# PLL_ADF4169.net
KiCad netlist of a schematic drawn in Altium Designer
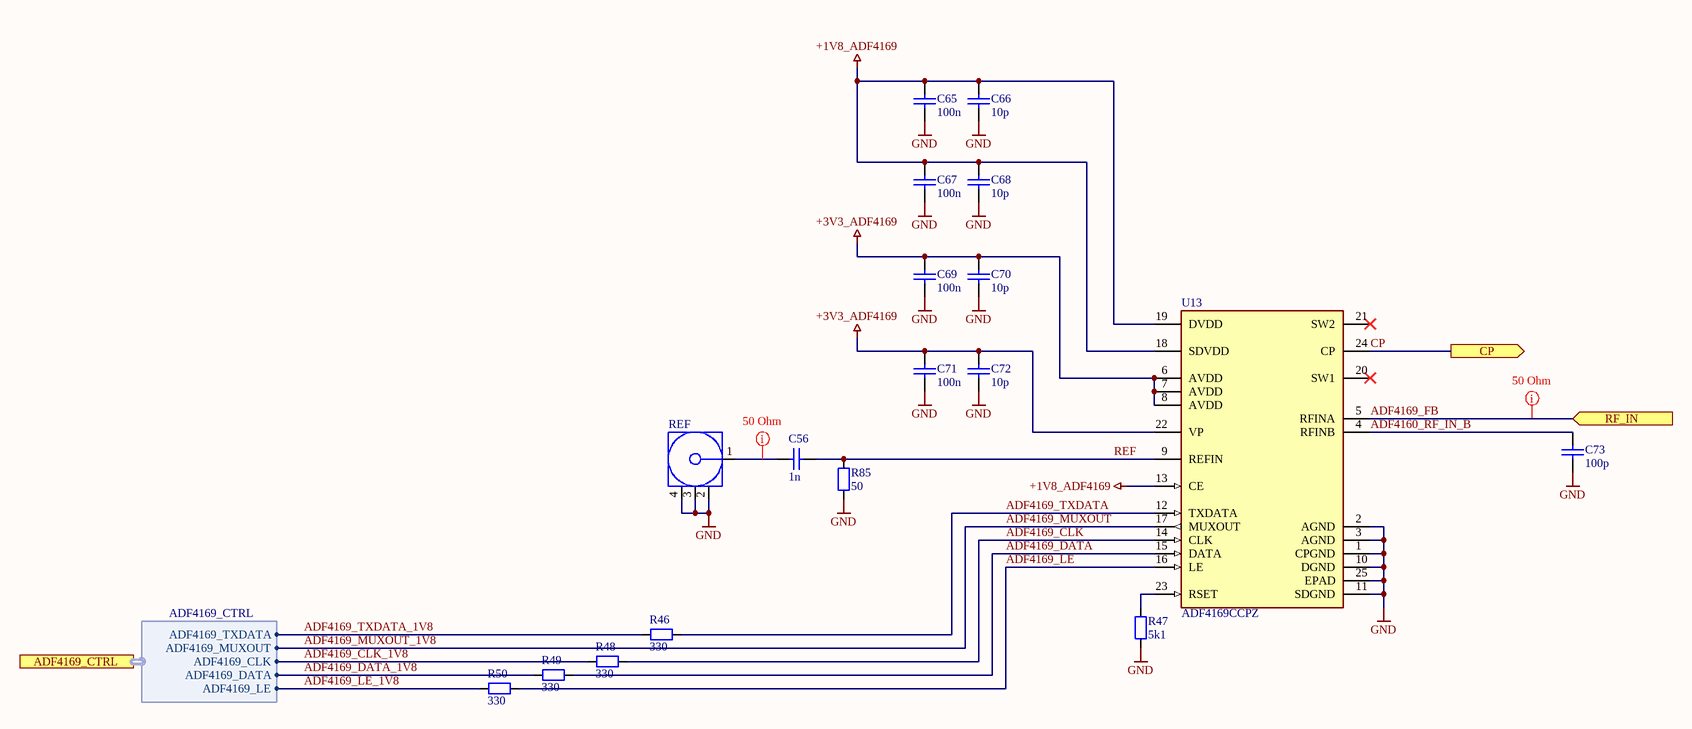
[diagram p0: PLL_ADF4169.SchDoc]

(export (version "E")
  (design (tool "Eeschema 10.0.6"))
  (components
    (comp (ref "C56")
      (value "1n")
      (footprint "C_0402_1005Metric_IPC_N")
      (description "Generic MLCC with 0402 Footprint")
      (fields (field (name "TOLERANCE") "5%"))
      (libsource (lib "database_library") (part "Capacitor_unpol"))
    )
    (comp (ref "C65")
      (value "100n")
      (footprint "C_0402_1005Metric_IPC_N")
      (description "Generic MLCC with 0402 Footprint")
      (fields (field (name "TOLERANCE") "10%"))
      (libsource (lib "database_library") (part "Capacitor_unpol"))
    )
    (comp (ref "C66")
      (value "10p")
      (footprint "C_0402_1005Metric_IPC_N")
      (description "Generic MLCC with 0402 Footprint")
      (fields (field (name "TOLERANCE") "0.5p"))
      (libsource (lib "database_library") (part "Capacitor_unpol"))
    )
    (comp (ref "C67")
      (value "100n")
      (footprint "C_0402_1005Metric_IPC_N")
      (description "Generic MLCC with 0402 Footprint")
      (fields (field (name "TOLERANCE") "10%"))
      (libsource (lib "database_library") (part "Capacitor_unpol"))
    )
    (comp (ref "C68")
      (value "10p")
      (footprint "C_0402_1005Metric_IPC_N")
      (description "Generic MLCC with 0402 Footprint")
      (fields (field (name "TOLERANCE") "0.5p"))
      (libsource (lib "database_library") (part "Capacitor_unpol"))
    )
    (comp (ref "C69")
      (value "100n")
      (footprint "C_0402_1005Metric_IPC_N")
      (description "Generic MLCC with 0402 Footprint")
      (fields (field (name "TOLERANCE") "10%"))
      (libsource (lib "database_library") (part "Capacitor_unpol"))
    )
    (comp (ref "C70")
      (value "10p")
      (footprint "C_0402_1005Metric_IPC_N")
      (description "Generic MLCC with 0402 Footprint")
      (fields (field (name "TOLERANCE") "0.5p"))
      (libsource (lib "database_library") (part "Capacitor_unpol"))
    )
    (comp (ref "C71")
      (value "100n")
      (footprint "C_0402_1005Metric_IPC_N")
      (description "Generic MLCC with 0402 Footprint")
      (fields (field (name "TOLERANCE") "10%"))
      (libsource (lib "database_library") (part "Capacitor_unpol"))
    )
    (comp (ref "C72")
      (value "10p")
      (footprint "C_0402_1005Metric_IPC_N")
      (description "Generic MLCC with 0402 Footprint")
      (fields (field (name "TOLERANCE") "0.5p"))
      (libsource (lib "database_library") (part "Capacitor_unpol"))
    )
    (comp (ref "C73")
      (value "100p")
      (footprint "C_0402_1005Metric_IPC_N")
      (description "Generic MLCC with 0402 Footprint")
      (libsource (lib "database_library") (part "Capacitor_unpol"))
    )
    (comp (ref "R46")
      (value "330")
      (footprint "R_0402_1005Metric_IPC_N")
      (description "Generic Chip Resistor with 0402 Footprint")
      (libsource (lib "database_library") (part "Resistor"))
    )
    (comp (ref "R47")
      (value "5k1")
      (footprint "R_0402_1005Metric_IPC_N")
      (description "Generic Chip Resistor with 0402 Footprint")
      (fields (field (name "TOLERANCE") "1%"))
      (libsource (lib "database_library") (part "Resistor"))
    )
    (comp (ref "R48")
      (value "330")
      (footprint "R_0402_1005Metric_IPC_N")
      (description "Generic Chip Resistor with 0402 Footprint")
      (libsource (lib "database_library") (part "Resistor"))
    )
    (comp (ref "R49")
      (value "330")
      (footprint "R_0402_1005Metric_IPC_N")
      (description "Generic Chip Resistor with 0402 Footprint")
      (libsource (lib "database_library") (part "Resistor"))
    )
    (comp (ref "R50")
      (value "330")
      (footprint "R_0402_1005Metric_IPC_N")
      (description "Generic Chip Resistor with 0402 Footprint")
      (libsource (lib "database_library") (part "Resistor"))
    )
    (comp (ref "R85")
      (value "50")
      (footprint "R_0402_1005Metric_IPC_N")
      (description "Generic Chip Resistor with 0402 Footprint")
      (libsource (lib "database_library") (part "Resistor"))
    )
    (comp (ref "REF")
      (value "60312862112552")
      (footprint "60312862112552")
      (description "WR-SMA Connector, PCB Solderless, DC~18GHz, 50Ohm")
      (fields (field (name "MANUFACTURER") "Würth"))
      (libsource (lib "database_library") (part "60312862112552"))
    )
    (comp (ref "U13")
      (value "ADF4169CCPZ")
      (footprint "LFCSP-WQ-24-1EP_4x4mm_P0.5mm_EP2.1x2.1mm_IPC_N")
      (fields (field (name "MANUFACTURER") "Analog Devices"))
      (libsource (lib "database_library") (part "ADF4169"))
    )
  )
  (nets
    (net (code "2") (name "+1V8_ADF4169") (class "Default")
      (node (ref "C65") (pin "2") (pinfunction "2_2") (pintype "passive"))
      (node (ref "C66") (pin "2") (pinfunction "2_2") (pintype "passive"))
      (node (ref "C67") (pin "2") (pinfunction "2_2") (pintype "passive"))
      (node (ref "C68") (pin "2") (pinfunction "2_2") (pintype "passive"))
      (node (ref "U13") (pin "13") (pinfunction "CE_13") (pintype "input"))
      (node (ref "U13") (pin "18") (pinfunction "SDVDD_18") (pintype "power_in"))
      (node (ref "U13") (pin "19") (pinfunction "DVDD_19") (pintype "power_in"))
    )
    (net (code "3") (name "+3V3_ADF4169") (class "Default")
      (node (ref "C69") (pin "2") (pinfunction "2_2") (pintype "passive"))
      (node (ref "C70") (pin "2") (pinfunction "2_2") (pintype "passive"))
      (node (ref "C71") (pin "2") (pinfunction "2_2") (pintype "passive"))
      (node (ref "C72") (pin "2") (pinfunction "2_2") (pintype "passive"))
      (node (ref "U13") (pin "22") (pinfunction "VP_22") (pintype "power_in"))
      (node (ref "U13") (pin "6") (pinfunction "AVDD_6") (pintype "power_in"))
      (node (ref "U13") (pin "7") (pinfunction "AVDD_7") (pintype "power_in"))
      (node (ref "U13") (pin "8") (pinfunction "AVDD_8") (pintype "power_in"))
    )
    (net (code "4") (name "/ADF4160_RF_IN_B") (class "Default")
      (node (ref "C73") (pin "2") (pinfunction "2_2") (pintype "passive"))
      (node (ref "U13") (pin "4") (pinfunction "RFINB_4") (pintype "passive"))
    )
    (net (code "5") (name "/ADF4169_CLK") (class "Default")
      (node (ref "R48") (pin "2") (pinfunction "2_2") (pintype "passive"))
      (node (ref "U13") (pin "14") (pinfunction "CLK_14") (pintype "input"))
    )
    (net (code "6") (name "/ADF4169_CLK_1V8") (class "Default")
      (node (ref "R48") (pin "1") (pinfunction "1_1") (pintype "passive"))
    )
    (net (code "7") (name "/ADF4169_DATA") (class "Default")
      (node (ref "R49") (pin "2") (pinfunction "2_2") (pintype "passive"))
      (node (ref "U13") (pin "15") (pinfunction "DATA_15") (pintype "input"))
    )
    (net (code "8") (name "/ADF4169_DATA_1V8") (class "Default")
      (node (ref "R49") (pin "1") (pinfunction "1_1") (pintype "passive"))
    )
    (net (code "9") (name "/ADF4169_FB") (class "Default")
      (node (ref "U13") (pin "5") (pinfunction "RFINA_5") (pintype "passive"))
    )
    (net (code "10") (name "/ADF4169_LE") (class "Default")
      (node (ref "R50") (pin "2") (pinfunction "2_2") (pintype "passive"))
      (node (ref "U13") (pin "16") (pinfunction "LE_16") (pintype "input"))
    )
    (net (code "11") (name "/ADF4169_LE_1V8") (class "Default")
      (node (ref "R50") (pin "1") (pinfunction "1_1") (pintype "passive"))
    )
    (net (code "12") (name "/ADF4169_MUXOUT") (class "Default")
      (node (ref "U13") (pin "17") (pinfunction "MUXOUT_17") (pintype "output"))
    )
    (net (code "13") (name "/ADF4169_TXDATA") (class "Default")
      (node (ref "R46") (pin "2") (pinfunction "2_2") (pintype "passive"))
      (node (ref "U13") (pin "12") (pinfunction "TXDATA_12") (pintype "input"))
    )
    (net (code "14") (name "/ADF4169_TXDATA_1V8") (class "Default")
      (node (ref "R46") (pin "1") (pinfunction "1_1") (pintype "passive"))
    )
    (net (code "15") (name "/CP") (class "Default")
      (node (ref "U13") (pin "24") (pinfunction "CP_24") (pintype "passive"))
    )
    (net (code "16") (name "/REF") (class "Default")
      (node (ref "C56") (pin "1") (pinfunction "1_1") (pintype "passive"))
      (node (ref "R85") (pin "2") (pinfunction "2_2") (pintype "passive"))
      (node (ref "U13") (pin "9") (pinfunction "REFIN_9") (pintype "passive"))
    )
    (net (code "18") (name "GND") (class "Default")
      (node (ref "C65") (pin "1") (pinfunction "1_1") (pintype "passive"))
      (node (ref "C66") (pin "1") (pinfunction "1_1") (pintype "passive"))
      (node (ref "C67") (pin "1") (pinfunction "1_1") (pintype "passive"))
      (node (ref "C68") (pin "1") (pinfunction "1_1") (pintype "passive"))
      (node (ref "C69") (pin "1") (pinfunction "1_1") (pintype "passive"))
      (node (ref "C70") (pin "1") (pinfunction "1_1") (pintype "passive"))
      (node (ref "C71") (pin "1") (pinfunction "1_1") (pintype "passive"))
      (node (ref "C72") (pin "1") (pinfunction "1_1") (pintype "passive"))
      (node (ref "C73") (pin "1") (pinfunction "1_1") (pintype "passive"))
      (node (ref "R47") (pin "1") (pinfunction "1_1") (pintype "passive"))
      (node (ref "R85") (pin "1") (pinfunction "1_1") (pintype "passive"))
      (node (ref "REF") (pin "2") (pinfunction "GND_2") (pintype "passive"))
      (node (ref "REF") (pin "3") (pinfunction "GND_3") (pintype "passive"))
      (node (ref "REF") (pin "4") (pinfunction "GND_4") (pintype "passive"))
      (node (ref "U13") (pin "1") (pinfunction "CPGND_1") (pintype "power_in"))
      (node (ref "U13") (pin "10") (pinfunction "DGND_10") (pintype "power_in"))
      (node (ref "U13") (pin "11") (pinfunction "SDGND_11") (pintype "power_in"))
      (node (ref "U13") (pin "2") (pinfunction "AGND_2") (pintype "power_in"))
      (node (ref "U13") (pin "25") (pinfunction "EPAD_25") (pintype "power_in"))
      (node (ref "U13") (pin "3") (pinfunction "AGND_3") (pintype "power_in"))
    )
    (net (code "19") (name "Net-(REF-Signal)") (class "Default")
      (node (ref "C56") (pin "2") (pinfunction "2_2") (pintype "passive"))
      (node (ref "REF") (pin "1") (pinfunction "Signal_1") (pintype "passive"))
    )
    (net (code "20") (name "Net-(U13-RSET)") (class "Default")
      (node (ref "R47") (pin "2") (pinfunction "2_2") (pintype "passive"))
      (node (ref "U13") (pin "23") (pinfunction "RSET_23") (pintype "input"))
    )
    (net (code "21") (name "unconnected-(U13-SW1-Pad20)") (class "Default")
      (node (ref "U13") (pin "20") (pinfunction "SW1_20") (pintype "passive+no_connect"))
    )
    (net (code "22") (name "unconnected-(U13-SW2-Pad21)") (class "Default")
      (node (ref "U13") (pin "21") (pinfunction "SW2_21") (pintype "passive+no_connect"))
    )
  )
)
